# second_flight_computer.net
KiCad netlist of a schematic drawn in EAGLE
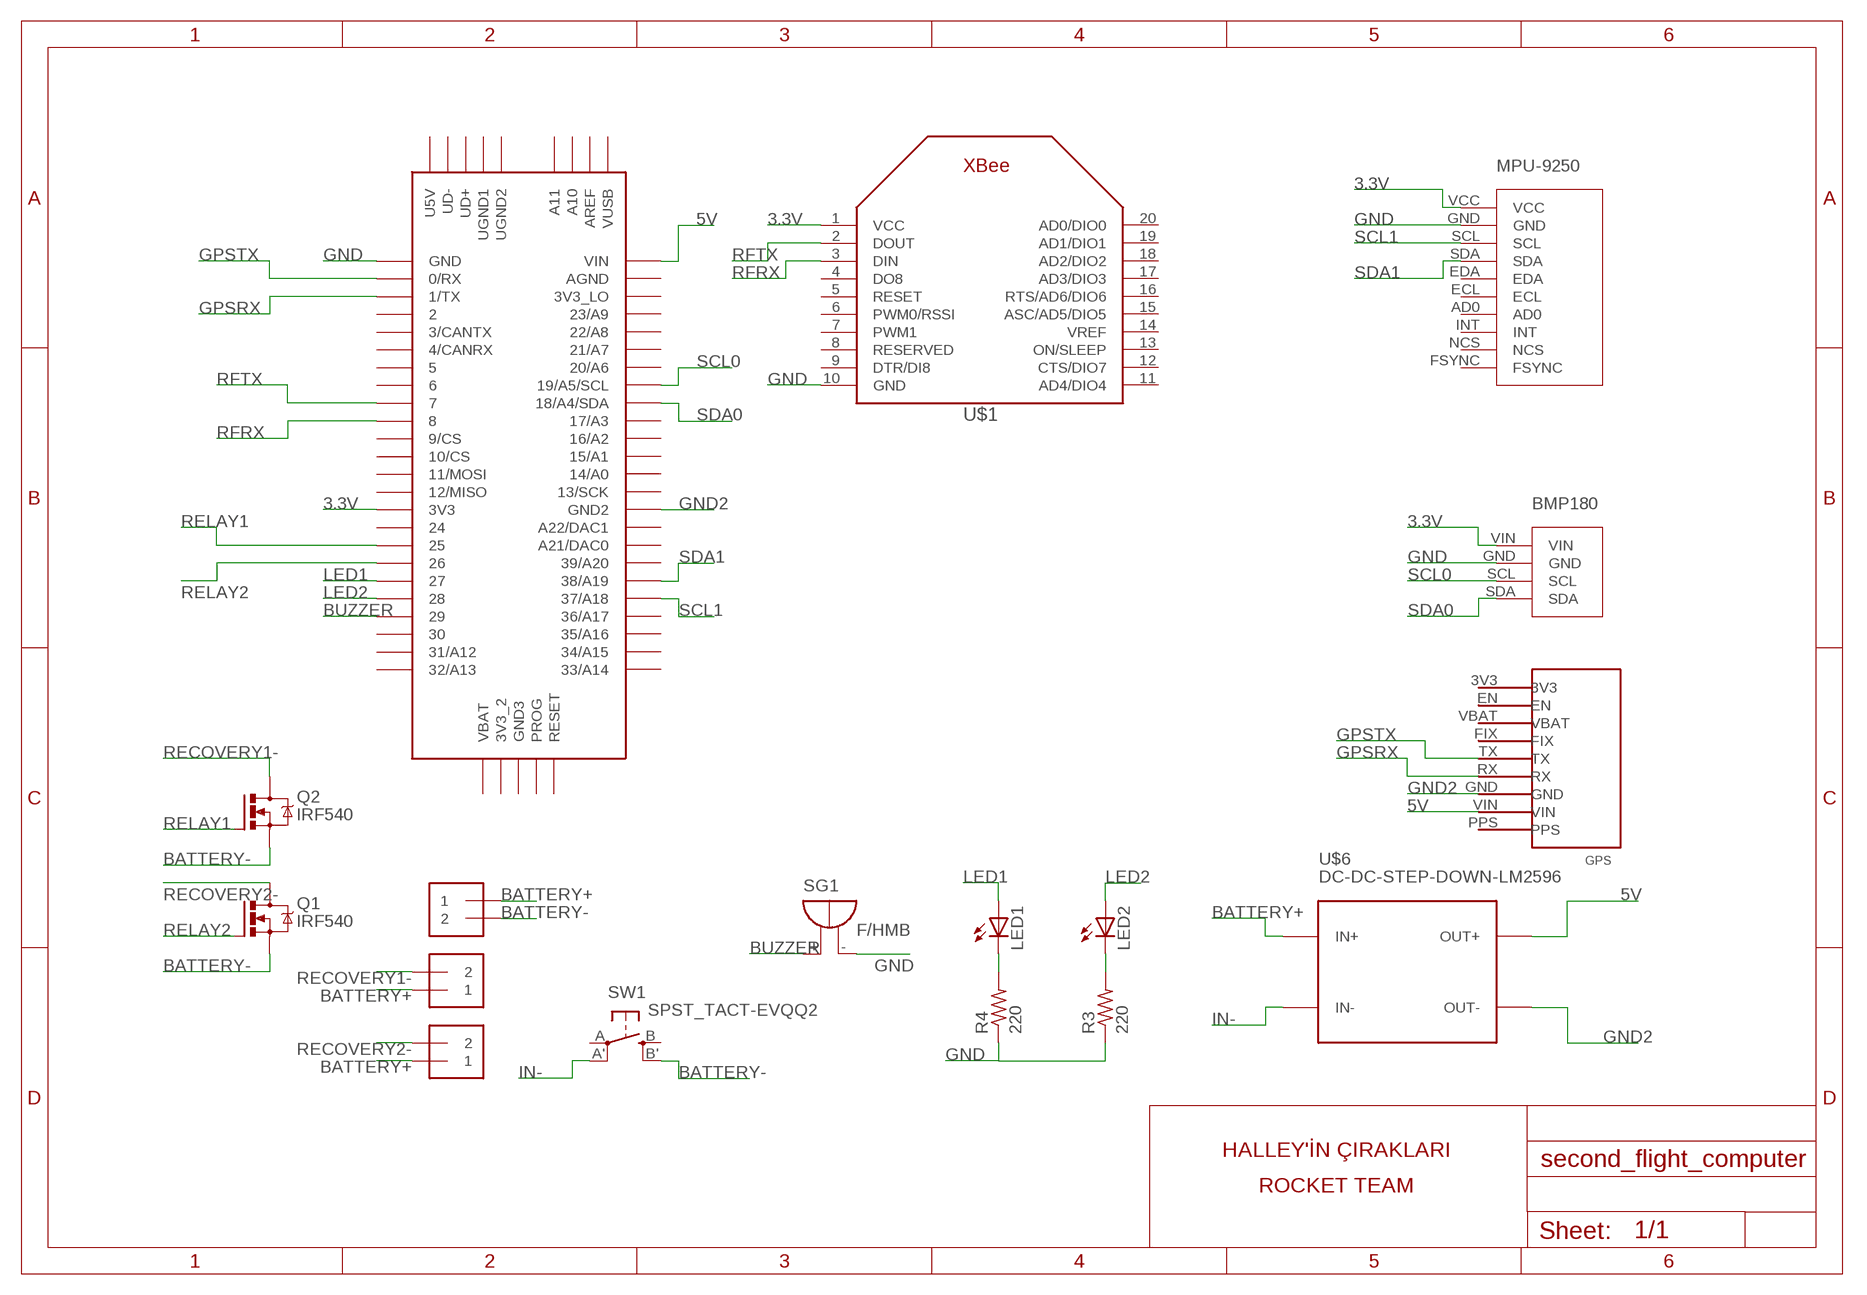
[diagram p0: schematic, sheet 1]

(export (version "E")
  (design (tool "Eeschema 10.0.6"))
  (components
    (comp (ref "BMP1")
      (value "BMP180")
      (footprint "eagle-import:BMP180")
      (libsource (lib "eagle-import") (part "BMP180"))
    )
    (comp (ref "J1")
      (value "1X2-3.5MM")
      (footprint "eagle-import:1X2-3.5MM")
      (libsource (lib "eagle-import") (part "1X2-3.5MM"))
    )
    (comp (ref "J2")
      (value "1X2-3.5MM")
      (footprint "eagle-import:1X2-3.5MM")
      (libsource (lib "eagle-import") (part "1X2-3.5MM"))
    )
    (comp (ref "J3")
      (value "1X2-3.5MM")
      (footprint "eagle-import:1X2-3.5MM")
      (libsource (lib "eagle-import") (part "1X2-3.5MM"))
    )
    (comp (ref "LED1")
      (value "LED5MM")
      (footprint "eagle-import:LED5MM")
      (libsource (lib "eagle-import") (part "LED5MM"))
    )
    (comp (ref "LED2")
      (value "LED5MM")
      (footprint "eagle-import:LED5MM")
      (libsource (lib "eagle-import") (part "LED5MM"))
    )
    (comp (ref "MPU-1")
      (value "MPU-9250")
      (footprint "eagle-import:MPU-9250")
      (libsource (lib "eagle-import") (part "MPU-9250"))
    )
    (comp (ref "Q1")
      (value "IRF540")
      (footprint "eagle-import:TO220BV")
      (fields (field (name "MANUFACTURER") "Infineon Technologies") (field (name "MPN") "IRF540NPBF"))
      (libsource (lib "eagle-import") (part "NMOSFET_-TO220IRF540"))
    )
    (comp (ref "Q2")
      (value "IRF540")
      (footprint "eagle-import:TO220BV")
      (fields (field (name "MANUFACTURER") "Infineon Technologies") (field (name "MPN") "IRF540NPBF"))
      (libsource (lib "eagle-import") (part "NMOSFET_-TO220IRF540"))
    )
    (comp (ref "R3")
      (value "220")
      (footprint "eagle-import:0204_7")
      (libsource (lib "eagle-import") (part "R-US_0204/7"))
    )
    (comp (ref "R4")
      (value "220")
      (footprint "eagle-import:0204_7")
      (libsource (lib "eagle-import") (part "R-US_0204/7"))
    )
    (comp (ref "SG1")
      (value "F/HMB")
      (footprint "eagle-import:F_HMB")
      (libsource (lib "eagle-import") (part "F/HMB"))
    )
    (comp (ref "SW1")
      (value "SPST_TACT-EVQQ2")
      (footprint "eagle-import:EVQ-Q2")
      (libsource (lib "eagle-import") (part "SPST_TACT-EVQQ2"))
    )
    (comp (ref "U$1")
      (value "XBEE")
      (footprint "eagle-import:XBEE")
      (libsource (lib "eagle-import") (part "XBEE"))
    )
    (comp (ref "U$3")
      (value "TEENSY_3.5/3.6")
      (footprint "eagle-import:TEENSY_3.5_3.6")
      (libsource (lib "eagle-import") (part "TEENSY_3.5/3.6"))
    )
    (comp (ref "U$5")
      (value "GPS")
      (footprint "eagle-import:GPS")
      (libsource (lib "eagle-import") (part "GPS"))
    )
    (comp (ref "U$6")
      (value "DC-DC-STEP-DOWN-LM2596")
      (footprint "eagle-import:DC-DC-STEP-DOWN-LM2596")
      (libsource (lib "eagle-import") (part "DC-DC-STEP-DOWN-LM2596"))
    )
  )
  (nets
    (net (code "1") (name "/3.3V") (class "Default")
      (node (ref "BMP1") (pin "VIN") (pinfunction "VIN_VIN") (pintype "bidirectional"))
      (node (ref "MPU-1") (pin "VCC") (pinfunction "VCC_VCC") (pintype "bidirectional"))
      (node (ref "U$1") (pin "1") (pinfunction "VCC_1") (pintype "power_in"))
      (node (ref "U$3") (pin "3V3") (pinfunction "3V3_3V3") (pintype "bidirectional"))
    )
    (net (code "2") (name "/5V") (class "Default")
      (node (ref "U$3") (pin "VIN") (pinfunction "VIN_VIN") (pintype "bidirectional"))
      (node (ref "U$5") (pin "VIN") (pinfunction "VIN_VIN") (pintype "bidirectional"))
      (node (ref "U$6") (pin "OUT+") (pinfunction "OUT+_OUT+") (pintype "bidirectional"))
    )
    (net (code "3") (name "/BATTERY+") (class "Default")
      (node (ref "J1") (pin "1") (pinfunction "1_1") (pintype "passive"))
      (node (ref "J2") (pin "1") (pinfunction "1_1") (pintype "passive"))
      (node (ref "J3") (pin "1") (pinfunction "1_1") (pintype "passive"))
      (node (ref "U$6") (pin "IN+") (pinfunction "IN+_IN+") (pintype "bidirectional"))
    )
    (net (code "4") (name "/BATTERY-") (class "Default")
      (node (ref "J1") (pin "2") (pinfunction "2_2") (pintype "passive"))
      (node (ref "Q1") (pin "S") (pinfunction "S_S") (pintype "passive"))
      (node (ref "Q2") (pin "S") (pinfunction "S_S") (pintype "passive"))
      (node (ref "SW1") (pin "B'") (pinfunction "S1_B'") (pintype "passive"))
    )
    (net (code "5") (name "/BUZZER") (class "Default")
      (node (ref "SG1") (pin "+") (pinfunction "+_+") (pintype "passive"))
      (node (ref "U$3") (pin "29") (pinfunction "29_29") (pintype "bidirectional"))
    )
    (net (code "6") (name "/GND") (class "Default")
      (node (ref "BMP1") (pin "GND") (pinfunction "GND_GND") (pintype "bidirectional"))
      (node (ref "MPU-1") (pin "GND") (pinfunction "GND_GND") (pintype "bidirectional"))
      (node (ref "R3") (pin "1") (pinfunction "1_1") (pintype "passive"))
      (node (ref "R4") (pin "1") (pinfunction "1_1") (pintype "passive"))
      (node (ref "SG1") (pin "-") (pinfunction "-_-") (pintype "passive"))
      (node (ref "U$1") (pin "10") (pinfunction "GND_10") (pintype "power_in"))
      (node (ref "U$3") (pin "GND") (pinfunction "GND_GND") (pintype "bidirectional"))
    )
    (net (code "7") (name "/GND2") (class "Default")
      (node (ref "U$3") (pin "GND2") (pinfunction "GND2_GND2") (pintype "bidirectional"))
      (node (ref "U$5") (pin "GND") (pinfunction "GND_GND") (pintype "bidirectional"))
      (node (ref "U$6") (pin "OUT-") (pinfunction "OUT-_OUT-") (pintype "bidirectional"))
    )
    (net (code "8") (name "/GPSRX") (class "Default")
      (node (ref "U$3") (pin "1/TX") (pinfunction "1/TX_1/TX") (pintype "bidirectional"))
      (node (ref "U$5") (pin "RX") (pinfunction "RX_RX") (pintype "bidirectional"))
    )
    (net (code "9") (name "/GPSTX") (class "Default")
      (node (ref "U$3") (pin "0/RX") (pinfunction "0/RX_0/RX") (pintype "bidirectional"))
      (node (ref "U$5") (pin "TX") (pinfunction "TX_TX") (pintype "bidirectional"))
    )
    (net (code "10") (name "/IN-") (class "Default")
      (node (ref "SW1") (pin "A'") (pinfunction "P1_A'") (pintype "passive"))
      (node (ref "U$6") (pin "IN-") (pinfunction "IN-_IN-") (pintype "bidirectional"))
    )
    (net (code "11") (name "/LED1") (class "Default")
      (node (ref "LED1") (pin "A") (pinfunction "A_A") (pintype "passive"))
      (node (ref "U$3") (pin "27") (pinfunction "27_27") (pintype "bidirectional"))
    )
    (net (code "12") (name "/LED2") (class "Default")
      (node (ref "LED2") (pin "A") (pinfunction "A_A") (pintype "passive"))
      (node (ref "U$3") (pin "28") (pinfunction "28_28") (pintype "bidirectional"))
    )
    (net (code "13") (name "/RECOVERY1-") (class "Default")
      (node (ref "J2") (pin "2") (pinfunction "2_2") (pintype "passive"))
      (node (ref "Q2") (pin "D") (pinfunction "D_D") (pintype "passive"))
    )
    (net (code "14") (name "/RECOVERY2-") (class "Default")
      (node (ref "J3") (pin "2") (pinfunction "2_2") (pintype "passive"))
      (node (ref "Q1") (pin "D") (pinfunction "D_D") (pintype "passive"))
    )
    (net (code "15") (name "/RELAY1") (class "Default")
      (node (ref "Q2") (pin "G") (pinfunction "G_G") (pintype "passive"))
      (node (ref "U$3") (pin "25") (pinfunction "25_25") (pintype "bidirectional"))
    )
    (net (code "16") (name "/RELAY2") (class "Default")
      (node (ref "Q1") (pin "G") (pinfunction "G_G") (pintype "passive"))
      (node (ref "U$3") (pin "26") (pinfunction "26_26") (pintype "bidirectional"))
    )
    (net (code "17") (name "/RFRX") (class "Default")
      (node (ref "U$1") (pin "3") (pinfunction "DIN_3") (pintype "input"))
      (node (ref "U$3") (pin "8") (pinfunction "8_8") (pintype "bidirectional"))
    )
    (net (code "18") (name "/RFTX") (class "Default")
      (node (ref "U$1") (pin "2") (pinfunction "DOUT_2") (pintype "output"))
      (node (ref "U$3") (pin "7") (pinfunction "7_7") (pintype "bidirectional"))
    )
    (net (code "19") (name "/SCL0") (class "Default")
      (node (ref "BMP1") (pin "SCL") (pinfunction "SCL_SCL") (pintype "bidirectional"))
      (node (ref "U$3") (pin "19/A5/SCL") (pinfunction "19/A5/SCL_19/A5/SCL") (pintype "bidirectional"))
    )
    (net (code "20") (name "/SCL1") (class "Default")
      (node (ref "MPU-1") (pin "SCL") (pinfunction "SCL_SCL") (pintype "bidirectional"))
      (node (ref "U$3") (pin "37/A18") (pinfunction "37/A18_37/A18") (pintype "bidirectional"))
    )
    (net (code "21") (name "/SDA0") (class "Default")
      (node (ref "BMP1") (pin "SDA") (pinfunction "SDA_SDA") (pintype "bidirectional"))
      (node (ref "U$3") (pin "18/A4/SDA") (pinfunction "18/A4/SDA_18/A4/SDA") (pintype "bidirectional"))
    )
    (net (code "22") (name "/SDA1") (class "Default")
      (node (ref "MPU-1") (pin "SDA") (pinfunction "SDA_SDA") (pintype "bidirectional"))
      (node (ref "U$3") (pin "38/A19") (pinfunction "38/A19_38/A19") (pintype "bidirectional"))
    )
    (net (code "23") (name "Net-(LED1-C)") (class "Default")
      (node (ref "LED1") (pin "K") (pinfunction "C_K") (pintype "passive"))
      (node (ref "R4") (pin "2") (pinfunction "2_2") (pintype "passive"))
    )
    (net (code "24") (name "Net-(LED2-C)") (class "Default")
      (node (ref "LED2") (pin "K") (pinfunction "C_K") (pintype "passive"))
      (node (ref "R3") (pin "2") (pinfunction "2_2") (pintype "passive"))
    )
    (net (code "25") (name "unconnected-(MPU-1-PadAD0)") (class "Default")
      (node (ref "MPU-1") (pin "AD0") (pinfunction "AD0_AD0") (pintype "bidirectional"))
    )
    (net (code "26") (name "unconnected-(MPU-1-PadECL)") (class "Default")
      (node (ref "MPU-1") (pin "ECL") (pinfunction "ECL_ECL") (pintype "bidirectional"))
    )
    (net (code "27") (name "unconnected-(MPU-1-PadEDA)") (class "Default")
      (node (ref "MPU-1") (pin "EDA") (pinfunction "EDA_EDA") (pintype "bidirectional"))
    )
    (net (code "28") (name "unconnected-(MPU-1-PadFSYNC)") (class "Default")
      (node (ref "MPU-1") (pin "FSYNC") (pinfunction "FSYNC_FSYNC") (pintype "bidirectional"))
    )
    (net (code "29") (name "unconnected-(MPU-1-PadINT)") (class "Default")
      (node (ref "MPU-1") (pin "INT") (pinfunction "INT_INT") (pintype "bidirectional"))
    )
    (net (code "30") (name "unconnected-(MPU-1-PadNCS)") (class "Default")
      (node (ref "MPU-1") (pin "NCS") (pinfunction "NCS_NCS") (pintype "bidirectional"))
    )
    (net (code "31") (name "unconnected-(SW1-P-PadA)") (class "Default")
      (node (ref "SW1") (pin "A") (pinfunction "P_A") (pintype "passive"))
    )
    (net (code "32") (name "unconnected-(SW1-S-PadB)") (class "Default")
      (node (ref "SW1") (pin "B") (pinfunction "S_B") (pintype "passive"))
    )
    (net (code "33") (name "unconnected-(U$1-AD0{slash}DIO0-Pad20)") (class "Default")
      (node (ref "U$1") (pin "20") (pinfunction "AD0/DIO0_20") (pintype "bidirectional"))
    )
    (net (code "34") (name "unconnected-(U$1-AD1{slash}DIO1-Pad19)") (class "Default")
      (node (ref "U$1") (pin "19") (pinfunction "AD1/DIO1_19") (pintype "bidirectional"))
    )
    (net (code "35") (name "unconnected-(U$1-AD2{slash}DIO2-Pad18)") (class "Default")
      (node (ref "U$1") (pin "18") (pinfunction "AD2/DIO2_18") (pintype "bidirectional"))
    )
    (net (code "36") (name "unconnected-(U$1-AD3{slash}DIO3-Pad17)") (class "Default")
      (node (ref "U$1") (pin "17") (pinfunction "AD3/DIO3_17") (pintype "bidirectional"))
    )
    (net (code "37") (name "unconnected-(U$1-AD4{slash}DIO4-Pad11)") (class "Default")
      (node (ref "U$1") (pin "11") (pinfunction "AD4/DIO4_11") (pintype "bidirectional"))
    )
    (net (code "38") (name "unconnected-(U$1-ASC{slash}AD5{slash}DIO5-Pad15)") (class "Default")
      (node (ref "U$1") (pin "15") (pinfunction "ASC/AD5/DIO5_15") (pintype "bidirectional"))
    )
    (net (code "39") (name "unconnected-(U$1-CTS{slash}DIO7-Pad12)") (class "Default")
      (node (ref "U$1") (pin "12") (pinfunction "CTS/DIO7_12") (pintype "bidirectional"))
    )
    (net (code "40") (name "unconnected-(U$1-DO8-Pad4)") (class "Default")
      (node (ref "U$1") (pin "4") (pinfunction "DO8_4") (pintype "output"))
    )
    (net (code "41") (name "unconnected-(U$1-DTR{slash}DI8-Pad9)") (class "Default")
      (node (ref "U$1") (pin "9") (pinfunction "DTR/DI8_9") (pintype "input"))
    )
    (net (code "42") (name "unconnected-(U$1-ON{slash}SLEEP-Pad13)") (class "Default")
      (node (ref "U$1") (pin "13") (pinfunction "ON/SLEEP_13") (pintype "output"))
    )
    (net (code "43") (name "unconnected-(U$1-PWM0{slash}RSSI-Pad6)") (class "Default")
      (node (ref "U$1") (pin "6") (pinfunction "PWM0/RSSI_6") (pintype "output"))
    )
    (net (code "44") (name "unconnected-(U$1-PWM1-Pad7)") (class "Default")
      (node (ref "U$1") (pin "7") (pinfunction "PWM1_7") (pintype "output"))
    )
    (net (code "45") (name "unconnected-(U$1-RESERVED-Pad8)") (class "Default")
      (node (ref "U$1") (pin "8") (pinfunction "RESERVED_8") (pintype "no_connect"))
    )
    (net (code "46") (name "unconnected-(U$1-RESET-Pad5)") (class "Default")
      (node (ref "U$1") (pin "5") (pinfunction "RESET_5") (pintype "input"))
    )
    (net (code "47") (name "unconnected-(U$1-RTS{slash}AD6{slash}DIO6-Pad16)") (class "Default")
      (node (ref "U$1") (pin "16") (pinfunction "RTS/AD6/DIO6_16") (pintype "bidirectional"))
    )
    (net (code "48") (name "unconnected-(U$1-VREF-Pad14)") (class "Default")
      (node (ref "U$1") (pin "14") (pinfunction "VREF_14") (pintype "input"))
    )
    (net (code "49") (name "unconnected-(U$3-A21{slash}DAC0-Pad21{slash}DAC0)") (class "Default")
      (node (ref "U$3") (pin "21/DAC0") (pinfunction "A21/DAC0_21/DAC0") (pintype "bidirectional"))
    )
    (net (code "50") (name "unconnected-(U$3-Pad2)") (class "Default")
      (node (ref "U$3") (pin "2") (pinfunction "2_2") (pintype "bidirectional"))
    )
    (net (code "51") (name "unconnected-(U$3-Pad3V3_2)") (class "Default")
      (node (ref "U$3") (pin "3V3_2") (pinfunction "3V3_2_3V3_2") (pintype "bidirectional"))
    )
    (net (code "52") (name "unconnected-(U$3-Pad3V3_LO)") (class "Default")
      (node (ref "U$3") (pin "3V3_LO") (pinfunction "3V3_LO_3V3_LO") (pintype "bidirectional"))
    )
    (net (code "53") (name "unconnected-(U$3-Pad3{slash}CANTX)") (class "Default")
      (node (ref "U$3") (pin "3/CANTX") (pinfunction "3/CANTX_3/CANTX") (pintype "bidirectional"))
    )
    (net (code "54") (name "unconnected-(U$3-Pad4{slash}CANRX)") (class "Default")
      (node (ref "U$3") (pin "4/CANRX") (pinfunction "4/CANRX_4/CANRX") (pintype "bidirectional"))
    )
    (net (code "55") (name "unconnected-(U$3-Pad5)") (class "Default")
      (node (ref "U$3") (pin "5") (pinfunction "5_5") (pintype "bidirectional"))
    )
    (net (code "56") (name "unconnected-(U$3-Pad6)") (class "Default")
      (node (ref "U$3") (pin "6") (pinfunction "6_6") (pintype "bidirectional"))
    )
    (net (code "57") (name "unconnected-(U$3-Pad9{slash}CS)") (class "Default")
      (node (ref "U$3") (pin "9/CS") (pinfunction "9/CS_9/CS") (pintype "bidirectional"))
    )
    (net (code "58") (name "unconnected-(U$3-Pad10{slash}CS)") (class "Default")
      (node (ref "U$3") (pin "10/CS") (pinfunction "10/CS_10/CS") (pintype "bidirectional"))
    )
    (net (code "59") (name "unconnected-(U$3-Pad11{slash}MOSI)") (class "Default")
      (node (ref "U$3") (pin "11/MOSI") (pinfunction "11/MOSI_11/MOSI") (pintype "bidirectional"))
    )
    (net (code "60") (name "unconnected-(U$3-Pad12{slash}MISO)") (class "Default")
      (node (ref "U$3") (pin "12/MISO") (pinfunction "12/MISO_12/MISO") (pintype "bidirectional"))
    )
    (net (code "61") (name "unconnected-(U$3-Pad13{slash}SCK)") (class "Default")
      (node (ref "U$3") (pin "13/SCK") (pinfunction "13/SCK_13/SCK") (pintype "bidirectional"))
    )
    (net (code "62") (name "unconnected-(U$3-Pad14{slash}A0)") (class "Default")
      (node (ref "U$3") (pin "14/A0") (pinfunction "14/A0_14/A0") (pintype "bidirectional"))
    )
    (net (code "63") (name "unconnected-(U$3-Pad15{slash}A1)") (class "Default")
      (node (ref "U$3") (pin "15/A1") (pinfunction "15/A1_15/A1") (pintype "bidirectional"))
    )
    (net (code "64") (name "unconnected-(U$3-Pad16{slash}A2)") (class "Default")
      (node (ref "U$3") (pin "16/A2") (pinfunction "16/A2_16/A2") (pintype "bidirectional"))
    )
    (net (code "65") (name "unconnected-(U$3-Pad17{slash}A3)") (class "Default")
      (node (ref "U$3") (pin "17/A3") (pinfunction "17/A3_17/A3") (pintype "bidirectional"))
    )
    (net (code "66") (name "unconnected-(U$3-Pad20{slash}A6)") (class "Default")
      (node (ref "U$3") (pin "20/A6") (pinfunction "20/A6_20/A6") (pintype "bidirectional"))
    )
    (net (code "67") (name "unconnected-(U$3-Pad21{slash}A7)") (class "Default")
      (node (ref "U$3") (pin "21/A7") (pinfunction "21/A7_21/A7") (pintype "bidirectional"))
    )
    (net (code "68") (name "unconnected-(U$3-Pad22{slash}A8)") (class "Default")
      (node (ref "U$3") (pin "22/A8") (pinfunction "22/A8_22/A8") (pintype "bidirectional"))
    )
    (net (code "69") (name "unconnected-(U$3-Pad23{slash}A9)") (class "Default")
      (node (ref "U$3") (pin "23/A9") (pinfunction "23/A9_23/A9") (pintype "bidirectional"))
    )
    (net (code "70") (name "unconnected-(U$3-Pad24)") (class "Default")
      (node (ref "U$3") (pin "24") (pinfunction "24_24") (pintype "bidirectional"))
    )
    (net (code "71") (name "unconnected-(U$3-Pad30)") (class "Default")
      (node (ref "U$3") (pin "30") (pinfunction "30_30") (pintype "bidirectional"))
    )
    (net (code "72") (name "unconnected-(U$3-Pad31{slash}A12)") (class "Default")
      (node (ref "U$3") (pin "31/A12") (pinfunction "31/A12_31/A12") (pintype "bidirectional"))
    )
    (net (code "73") (name "unconnected-(U$3-Pad32{slash}A13)") (class "Default")
      (node (ref "U$3") (pin "32/A13") (pinfunction "32/A13_32/A13") (pintype "bidirectional"))
    )
    (net (code "74") (name "unconnected-(U$3-Pad33{slash}A14)") (class "Default")
      (node (ref "U$3") (pin "33/A14") (pinfunction "33/A14_33/A14") (pintype "bidirectional"))
    )
    (net (code "75") (name "unconnected-(U$3-Pad34{slash}A15)") (class "Default")
      (node (ref "U$3") (pin "34/A15") (pinfunction "34/A15_34/A15") (pintype "bidirectional"))
    )
    (net (code "76") (name "unconnected-(U$3-Pad35{slash}A16)") (class "Default")
      (node (ref "U$3") (pin "35/A16") (pinfunction "35/A16_35/A16") (pintype "bidirectional"))
    )
    (net (code "77") (name "unconnected-(U$3-Pad36{slash}A17)") (class "Default")
      (node (ref "U$3") (pin "36/A17") (pinfunction "36/A17_36/A17") (pintype "bidirectional"))
    )
    (net (code "78") (name "unconnected-(U$3-Pad39{slash}A20)") (class "Default")
      (node (ref "U$3") (pin "39/A20") (pinfunction "39/A20_39/A20") (pintype "bidirectional"))
    )
    (net (code "79") (name "unconnected-(U$3-PadA10)") (class "Default")
      (node (ref "U$3") (pin "A10") (pinfunction "A10_A10") (pintype "bidirectional"))
    )
    (net (code "80") (name "unconnected-(U$3-PadA11)") (class "Default")
      (node (ref "U$3") (pin "A11") (pinfunction "A11_A11") (pintype "bidirectional"))
    )
    (net (code "81") (name "unconnected-(U$3-PadA22{slash}DAC1)") (class "Default")
      (node (ref "U$3") (pin "A22/DAC1") (pinfunction "A22/DAC1_A22/DAC1") (pintype "bidirectional"))
    )
    (net (code "82") (name "unconnected-(U$3-PadAGND)") (class "Default")
      (node (ref "U$3") (pin "AGND") (pinfunction "AGND_AGND") (pintype "bidirectional"))
    )
    (net (code "83") (name "unconnected-(U$3-PadAREF)") (class "Default")
      (node (ref "U$3") (pin "AREF") (pinfunction "AREF_AREF") (pintype "bidirectional"))
    )
    (net (code "84") (name "unconnected-(U$3-PadGND3)") (class "Default")
      (node (ref "U$3") (pin "GND3") (pinfunction "GND3_GND3") (pintype "bidirectional"))
    )
    (net (code "85") (name "unconnected-(U$3-PadPROG)") (class "Default")
      (node (ref "U$3") (pin "PROG") (pinfunction "PROG_PROG") (pintype "bidirectional"))
    )
    (net (code "86") (name "unconnected-(U$3-PadRESET)") (class "Default")
      (node (ref "U$3") (pin "RESET") (pinfunction "RESET_RESET") (pintype "bidirectional"))
    )
    (net (code "87") (name "unconnected-(U$3-PadU5V)") (class "Default")
      (node (ref "U$3") (pin "U5V") (pinfunction "U5V_U5V") (pintype "bidirectional"))
    )
    (net (code "88") (name "unconnected-(U$3-PadUD+)") (class "Default")
      (node (ref "U$3") (pin "UD+") (pinfunction "UD+_UD+") (pintype "bidirectional"))
    )
    (net (code "89") (name "unconnected-(U$3-PadUD-)") (class "Default")
      (node (ref "U$3") (pin "UD-") (pinfunction "UD-_UD-") (pintype "bidirectional"))
    )
    (net (code "90") (name "unconnected-(U$3-PadUGND1)") (class "Default")
      (node (ref "U$3") (pin "UGND1") (pinfunction "UGND1_UGND1") (pintype "bidirectional"))
    )
    (net (code "91") (name "unconnected-(U$3-PadUGND2)") (class "Default")
      (node (ref "U$3") (pin "UGND2") (pinfunction "UGND2_UGND2") (pintype "bidirectional"))
    )
    (net (code "92") (name "unconnected-(U$3-PadVBAT)") (class "Default")
      (node (ref "U$3") (pin "VBAT") (pinfunction "VBAT_VBAT") (pintype "bidirectional"))
    )
    (net (code "93") (name "unconnected-(U$3-PadVUSB)") (class "Default")
      (node (ref "U$3") (pin "VUSB") (pinfunction "VUSB_VUSB") (pintype "bidirectional"))
    )
    (net (code "94") (name "unconnected-(U$5-Pad3V3)") (class "Default")
      (node (ref "U$5") (pin "3V3") (pinfunction "3V3_3V3") (pintype "bidirectional"))
    )
    (net (code "95") (name "unconnected-(U$5-PadEN)") (class "Default")
      (node (ref "U$5") (pin "EN") (pinfunction "EN_EN") (pintype "bidirectional"))
    )
    (net (code "96") (name "unconnected-(U$5-PadFIX)") (class "Default")
      (node (ref "U$5") (pin "FIX") (pinfunction "FIX_FIX") (pintype "bidirectional"))
    )
    (net (code "97") (name "unconnected-(U$5-PadPPS)") (class "Default")
      (node (ref "U$5") (pin "PPS") (pinfunction "PPS_PPS") (pintype "bidirectional"))
    )
    (net (code "98") (name "unconnected-(U$5-PadVBAT)") (class "Default")
      (node (ref "U$5") (pin "VBAT") (pinfunction "VBAT_VBAT") (pintype "bidirectional"))
    )
  )
)
